# ESP32.net
KiCad netlist of a schematic drawn in Altium Designer
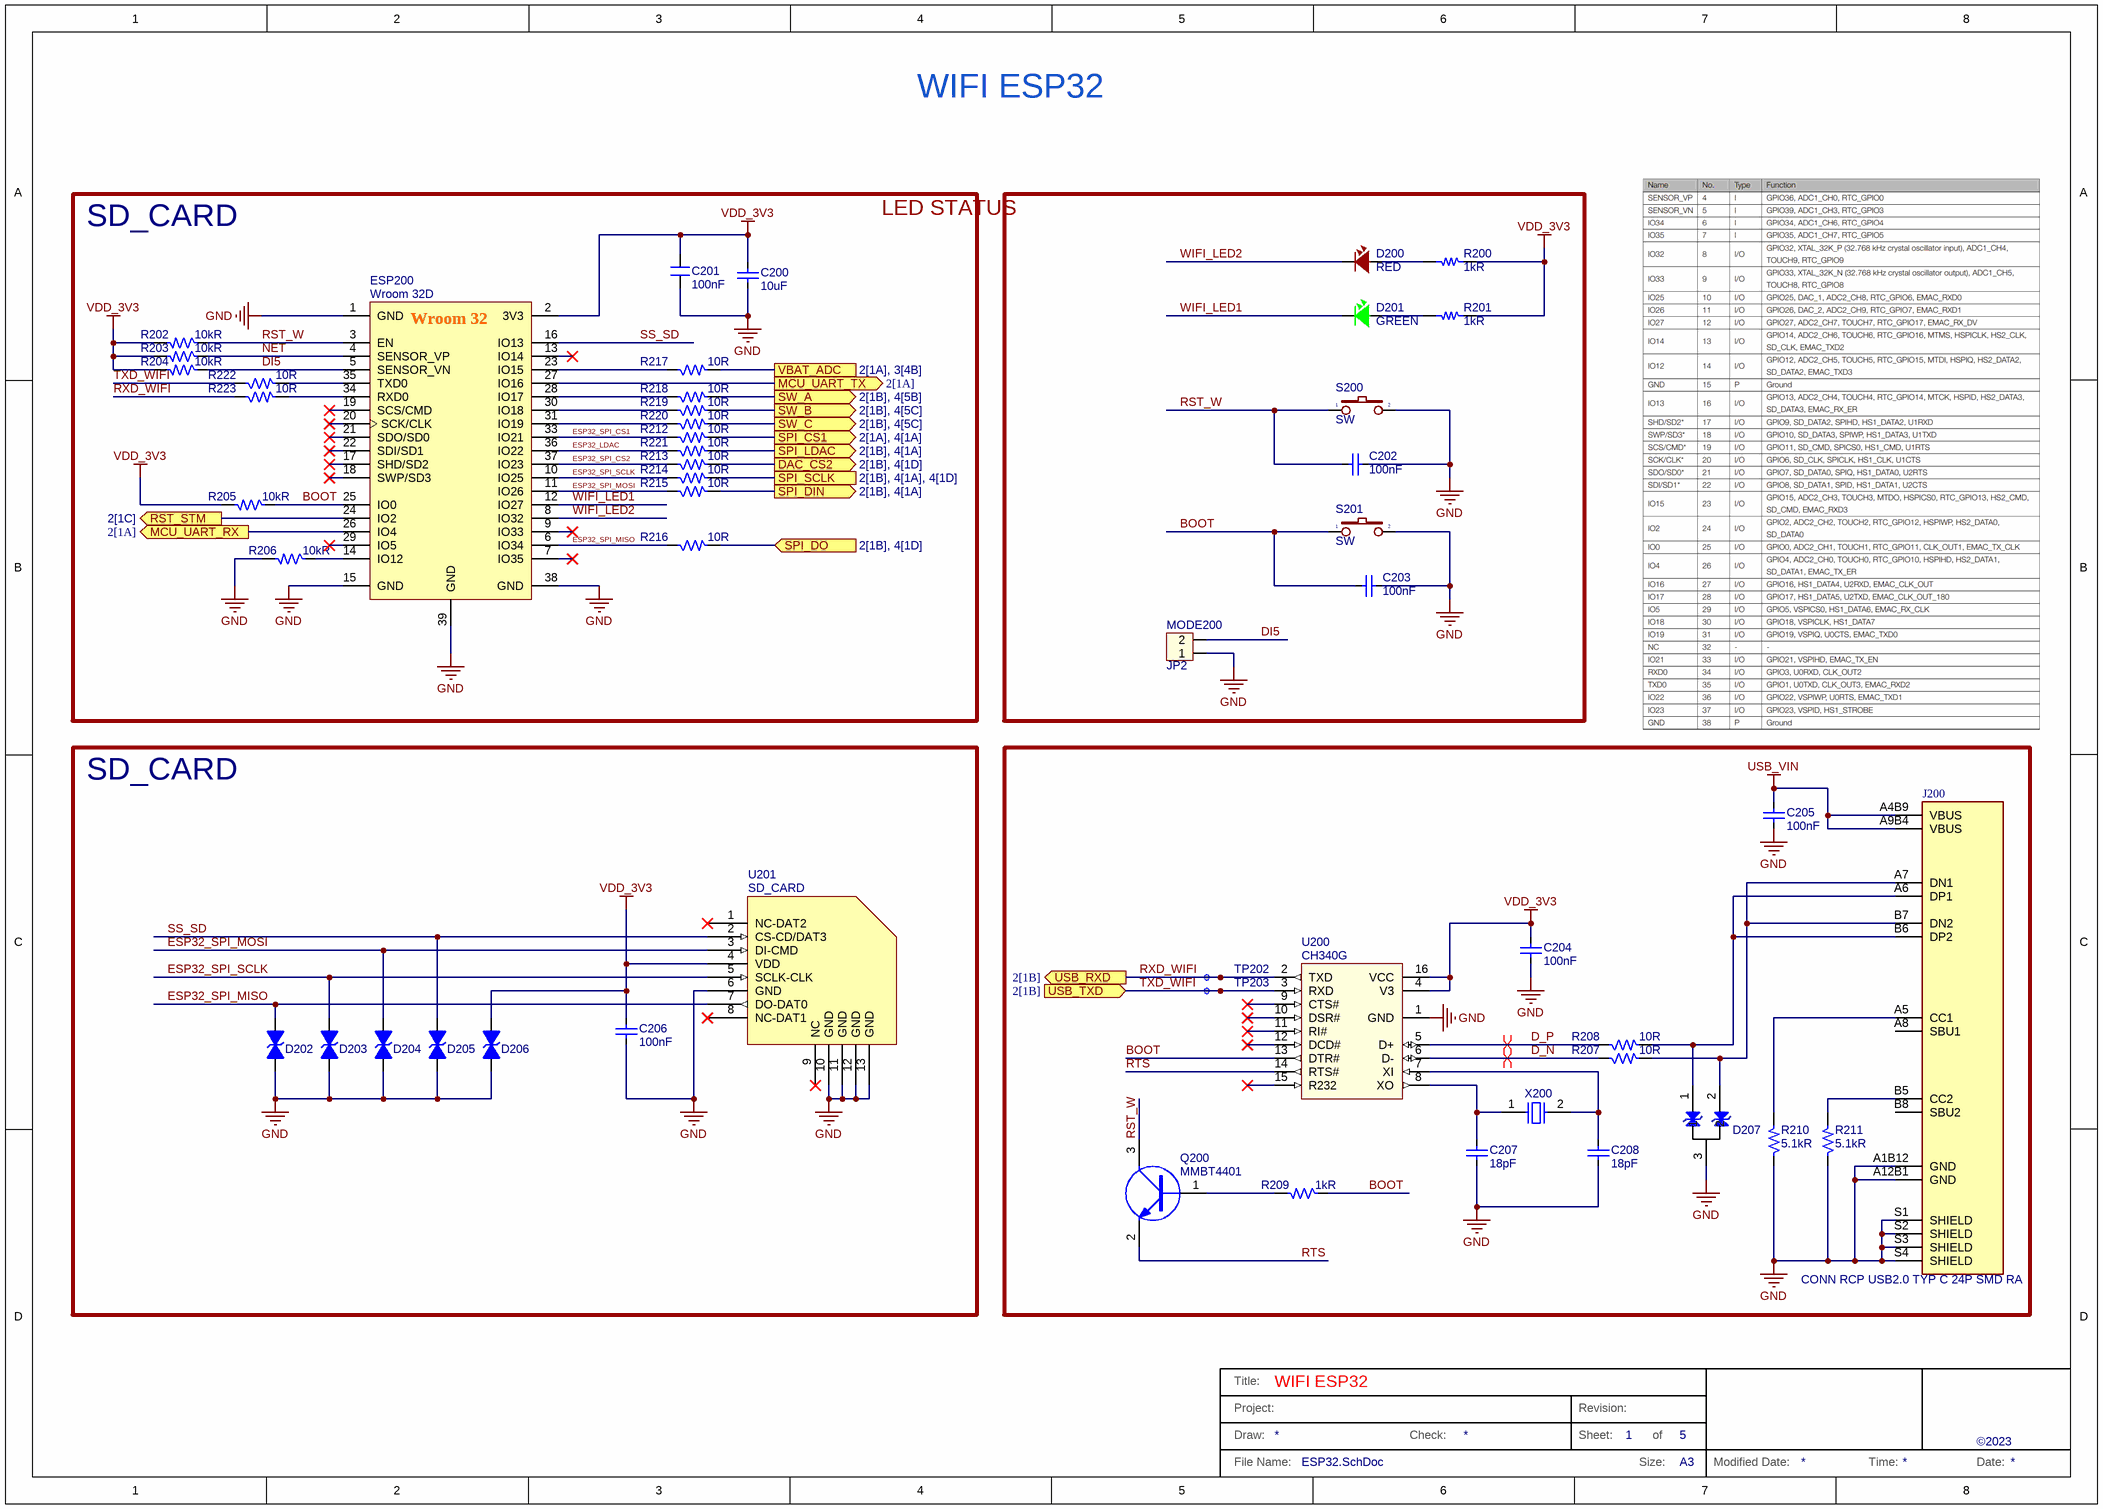
[diagram p0: ESP32.SchDoc]

(export (version "E")
  (design (tool "Eeschema 10.0.6"))
  (components
    (comp (ref "C200")
      (value "10uF")
      (footprint "C0805")
      (description "CAP CER 10UF 16V X5R 0603")
      (libsource (lib "My Library") (part "CapSMD"))
    )
    (comp (ref "C201")
      (value "100nF")
      (footprint "CAP0603-M")
      (description "CAP CER 100nF 16V X5R 0603")
      (fields (field (name "MANUFACTURER") "MURATA"))
      (libsource (lib "Selex_Component_Lib") (part "Cap_Cer_0603_10uF"))
    )
    (comp (ref "C202")
      (value "100nF")
      (footprint "CAP0603-M")
      (description "CAP CER 100nF 16V X5R 0603")
      (libsource (lib "My Library") (part "CapSMD"))
    )
    (comp (ref "C203")
      (value "100nF")
      (footprint "CAP0603-M")
      (description "CAP CER 100nF 16V X5R 0603")
      (libsource (lib "My Library") (part "CapSMD"))
    )
    (comp (ref "C204")
      (value "100nF")
      (footprint "CAP0603-M")
      (description "CAP CER 100nF 16V X5R 0603")
      (libsource (lib "My Library") (part "CapSMD"))
    )
    (comp (ref "C205")
      (value "100nF")
      (footprint "CAP0603-M")
      (description "CAP CER 100nF 16V X5R 0603")
      (libsource (lib "My Library") (part "CapSMD"))
    )
    (comp (ref "C206")
      (value "100nF")
      (footprint "CAP0603-M")
      (description "CAP CER 100nF 16V X5R 0603")
      (libsource (lib "My Library") (part "CapSMD"))
    )
    (comp (ref "C207")
      (value "18pF")
      (footprint "CAP0603-M")
      (description "CAP CER 18PF 50V C0G/NP0 0603")
      (libsource (lib "My Library") (part "CapSMD"))
    )
    (comp (ref "C208")
      (value "18pF")
      (footprint "CAP0603-M")
      (description "CAP CER 18PF 50V C0G/NP0 0603")
      (libsource (lib "My Library") (part "CapSMD"))
    )
    (comp (ref "D200")
      (value "RED")
      (footprint "LED-0603-Red")
      (description "LED RED")
      (libsource (lib "RTLS_Anchor") (part "LED_3"))
    )
    (comp (ref "D201")
      (value "GREEN")
      (footprint "LED-0603-Green")
      (description "LED GREEN")
      (libsource (lib "RTLS_Anchor") (part "LED_1"))
    )
    (comp (ref "D202")
      (value "ESDAXLC6-1BU2")
      (footprint "2-UDFN")
      (description "TVS DIODE 3VWM 17VC ST0201")
      (fields (field (name "MANUFACTURER") "STMicroelectronics"))
      (libsource (lib "RTLS_Anchor") (part "ESDAXLC6-1BU2"))
    )
    (comp (ref "D203")
      (value "ESDAXLC6-1BU2")
      (footprint "2-UDFN")
      (description "TVS DIODE 3VWM 17VC ST0201")
      (fields (field (name "MANUFACTURER") "STMicroelectronics"))
      (libsource (lib "RTLS_Anchor") (part "ESDAXLC6-1BU2"))
    )
    (comp (ref "D204")
      (value "ESDAXLC6-1BU2")
      (footprint "2-UDFN")
      (description "TVS DIODE 3VWM 17VC ST0201")
      (fields (field (name "MANUFACTURER") "STMicroelectronics"))
      (libsource (lib "RTLS_Anchor") (part "ESDAXLC6-1BU2"))
    )
    (comp (ref "D205")
      (value "ESDAXLC6-1BU2")
      (footprint "2-UDFN")
      (description "TVS DIODE 3VWM 17VC ST0201")
      (fields (field (name "MANUFACTURER") "STMicroelectronics"))
      (libsource (lib "RTLS_Anchor") (part "ESDAXLC6-1BU2"))
    )
    (comp (ref "D206")
      (value "ESDAXLC6-1BU2")
      (footprint "2-UDFN")
      (description "TVS DIODE 3VWM 17VC ST0201")
      (fields (field (name "MANUFACTURER") "STMicroelectronics"))
      (libsource (lib "RTLS_Anchor") (part "ESDAXLC6-1BU2"))
    )
    (comp (ref "D207")
      (value "DESD2CAN2SOQ-7")
      (footprint "SOT23-3")
      (description "TVS DIODE 24VWM 41VC SOT23")
      (fields (field (name "MANUFACTURER") "onsemi"))
      (libsource (lib "S1500_Diode") (part "NUP2105"))
    )
    (comp (ref "ESP200")
      (value "Wroom 32D")
      (footprint "ESP32_UE")
      (libsource (lib "PCB_LT") (part "ESP-WROOM-32"))
    )
    (comp (ref "J200")
      (value "CONN RCP USB2.0 TYP C 24P SMD RA")
      (footprint "USB_USB4110-GF-A")
      (description "Conn USB Type C RCP 16 POS 0.3mm/0.5mm Solder ST SMD 16 Terminal 1 Port T/R")
      (libsource (lib "EV_Mainboard") (part "USB_TypeC_USB4110-GF-A"))
    )
    (comp (ref "MODE200")
      (value "JP2")
      (footprint "XH2.54")
      (description "Connector 2")
      (libsource (lib "Anh_Trung") (part "Con2"))
    )
    (comp (ref "Q200")
      (value "MMBT4401")
      (footprint "SOT23-3")
      (description "NPN 600mW, ECB")
      (libsource (lib "Anh_Trung") (part "C1815"))
    )
    (comp (ref "R200")
      (value "1kR")
      (footprint "R_0603")
      (description "RES SMD 1K OHM 1% 1/8W 0603")
      (fields (field (name "MANUFACTURER") "Generic Components"))
      (libsource (lib "My Library") (part "Resistor - SMD"))
    )
    (comp (ref "R201")
      (value "1kR")
      (footprint "R_0603")
      (description "RES SMD 1K OHM 1% 1/8W 0603")
      (fields (field (name "MANUFACTURER") "Generic Components"))
      (libsource (lib "My Library") (part "Resistor - SMD"))
    )
    (comp (ref "R202")
      (value "10kR")
      (footprint "R_0603")
      (description "RES SMD 10K OHM 1% 1/8W 0603")
      (fields (field (name "MANUFACTURER") "Yageo"))
      (libsource (lib "Anh_Trung") (part "R"))
    )
    (comp (ref "R203")
      (value "10kR")
      (footprint "R_0603")
      (description "RES SMD 10K OHM 1% 1/8W 0603")
      (fields (field (name "MANUFACTURER") "Yageo"))
      (libsource (lib "Anh_Trung") (part "R"))
    )
    (comp (ref "R204")
      (value "10kR")
      (footprint "R_0603")
      (description "RES SMD 10K OHM 1% 1/8W 0603")
      (fields (field (name "MANUFACTURER") "Yageo"))
      (libsource (lib "Anh_Trung") (part "R"))
    )
    (comp (ref "R205")
      (value "10kR")
      (footprint "R_0603")
      (description "RES SMD 10K OHM 1% 1/8W 0603")
      (fields (field (name "MANUFACTURER") "Yageo"))
      (libsource (lib "Anh_Trung") (part "R"))
    )
    (comp (ref "R206")
      (value "10kR")
      (footprint "R_0603")
      (description "RES SMD 10K OHM 1% 1/8W 0603")
      (fields (field (name "MANUFACTURER") "Yageo"))
      (libsource (lib "Anh_Trung") (part "R"))
    )
    (comp (ref "R207")
      (value "10R")
      (footprint "R_0603")
      (description "RES SMD 10R OHM 1% 1/8W 0603")
      (fields (field (name "MANUFACTURER") "Yageo"))
      (libsource (lib "Anh_Trung") (part "R"))
    )
    (comp (ref "R208")
      (value "10R")
      (footprint "R_0603")
      (description "RES SMD 10R OHM 1% 1/8W 0603")
      (fields (field (name "MANUFACTURER") "Yageo"))
      (libsource (lib "Anh_Trung") (part "R"))
    )
    (comp (ref "R209")
      (value "1kR")
      (footprint "R_0603")
      (description "RES SMD 1K OHM 1% 1/8W 0603")
      (fields (field (name "MANUFACTURER") "Yageo"))
      (libsource (lib "Anh_Trung") (part "R"))
    )
    (comp (ref "R210")
      (value "5.1kR")
      (footprint "R_0603")
      (description "Resistor 1/4W")
      (fields (field (name "MANUFACTURER") "Yageo"))
      (libsource (lib "Anh_Trung") (part "R"))
    )
    (comp (ref "R211")
      (value "5.1kR")
      (footprint "R_0603")
      (description "Resistor 1/4W")
      (fields (field (name "MANUFACTURER") "Yageo"))
      (libsource (lib "Anh_Trung") (part "R"))
    )
    (comp (ref "R212")
      (value "10R")
      (footprint "R_0603")
      (description "RES SMD 10R OHM 1% 1/8W 0603")
      (fields (field (name "MANUFACTURER") "Yageo"))
      (libsource (lib "Anh_Trung") (part "R"))
    )
    (comp (ref "R213")
      (value "10R")
      (footprint "R_0603")
      (description "RES SMD 10R OHM 1% 1/8W 0603")
      (fields (field (name "MANUFACTURER") "Yageo"))
      (libsource (lib "Anh_Trung") (part "R"))
    )
    (comp (ref "R214")
      (value "10R")
      (footprint "R_0603")
      (description "RES SMD 10R OHM 1% 1/8W 0603")
      (fields (field (name "MANUFACTURER") "Yageo"))
      (libsource (lib "Anh_Trung") (part "R"))
    )
    (comp (ref "R215")
      (value "10R")
      (footprint "R_0603")
      (description "RES SMD 10R OHM 1% 1/8W 0603")
      (fields (field (name "MANUFACTURER") "Yageo"))
      (libsource (lib "Anh_Trung") (part "R"))
    )
    (comp (ref "R216")
      (value "10R")
      (footprint "R_0603")
      (description "RES SMD 10R OHM 1% 1/8W 0603")
      (fields (field (name "MANUFACTURER") "Yageo"))
      (libsource (lib "Anh_Trung") (part "R"))
    )
    (comp (ref "R217")
      (value "10R")
      (footprint "R_0603")
      (description "RES SMD 10R OHM 1% 1/8W 0603")
      (fields (field (name "MANUFACTURER") "Yageo"))
      (libsource (lib "Anh_Trung") (part "R"))
    )
    (comp (ref "R218")
      (value "10R")
      (footprint "R_0603")
      (description "RES SMD 10R OHM 1% 1/8W 0603")
      (fields (field (name "MANUFACTURER") "Yageo"))
      (libsource (lib "Anh_Trung") (part "R"))
    )
    (comp (ref "R219")
      (value "10R")
      (footprint "R_0603")
      (description "RES SMD 10R OHM 1% 1/8W 0603")
      (fields (field (name "MANUFACTURER") "Yageo"))
      (libsource (lib "Anh_Trung") (part "R"))
    )
    (comp (ref "R220")
      (value "10R")
      (footprint "R_0603")
      (description "RES SMD 10R OHM 1% 1/8W 0603")
      (fields (field (name "MANUFACTURER") "Yageo"))
      (libsource (lib "Anh_Trung") (part "R"))
    )
    (comp (ref "R221")
      (value "10R")
      (footprint "R_0603")
      (description "RES SMD 10R OHM 1% 1/8W 0603")
      (fields (field (name "MANUFACTURER") "Yageo"))
      (libsource (lib "Anh_Trung") (part "R"))
    )
    (comp (ref "R222")
      (value "10R")
      (footprint "R_0603")
      (description "RES SMD 10R OHM 1% 1/8W 0603")
      (fields (field (name "MANUFACTURER") "Yageo"))
      (libsource (lib "Anh_Trung") (part "R"))
    )
    (comp (ref "R223")
      (value "10R")
      (footprint "R_0603")
      (description "RES SMD 10R OHM 1% 1/8W 0603")
      (fields (field (name "MANUFACTURER") "Yageo"))
      (libsource (lib "Anh_Trung") (part "R"))
    )
    (comp (ref "S200")
      (value "SW")
      (footprint "BUTTON_2P_SMD")
      (description "Switch button 2 pin")
      (libsource (lib "Anh_Trung") (part "SW2"))
    )
    (comp (ref "S201")
      (value "SW")
      (footprint "BUTTON_2P_SMD")
      (description "Switch button 2 pin")
      (libsource (lib "Anh_Trung") (part "SW2"))
    )
    (comp (ref "TP202")
      (value "RXD")
      (footprint "TPH")
      (description "Test_Point_1mm")
      (libsource (lib "Selex_Component_Lib") (part "Test_Point_1mm"))
    )
    (comp (ref "TP203")
      (value "TXD")
      (footprint "TPH")
      (description "Test_Point_1mm")
      (libsource (lib "Selex_Component_Lib") (part "Test_Point_1mm"))
    )
    (comp (ref "U200")
      (value "CH340G")
      (footprint "SOIC-16")
      (description "USB to UART Interface")
      (fields (field (name "MANUFACTURER") "WCH"))
      (libsource (lib "Anh_Trung") (part "CH340G"))
    )
    (comp (ref "U201")
      (value "SD_CARD")
      (footprint "MICROSD2")
      (description "SD/MMC holder")
      (libsource (lib "Anh_Trung") (part "MicroSD"))
    )
    (comp (ref "X200")
      (value "WTL5G60391VH")
      (footprint "XTAL_SMD_3P5")
      (description "XTal 8Mhz")
      (fields (field (name "MANUFACTURER") "WTL"))
      (libsource (lib "S1600_Crystal_Oscillator") (part "Xtal_2P_SMD_5P0X3P5_8Mhz"))
    )
  )
  (nets
    (net (code "1") (name "/BOOT") (class "Default")
      (node (ref "C203") (pin "2") (pinfunction "2_2") (pintype "passive"))
      (node (ref "ESP200") (pin "25") (pinfunction "IO0_25") (pintype "passive"))
      (node (ref "R205") (pin "1") (pinfunction "1_1") (pintype "passive"))
      (node (ref "R209") (pin "1") (pinfunction "1_1") (pintype "passive"))
      (node (ref "S201") (pin "1") (pinfunction "1_1") (pintype "passive"))
      (node (ref "U200") (pin "13") (pinfunction "DTR#_13") (pintype "output"))
    )
    (net (code "2") (name "/DAC_CS2") (class "Default")
      (node (ref "R213") (pin "2") (pinfunction "2_2") (pintype "passive"))
    )
    (net (code "3") (name "/DI5") (class "Default")
      (node (ref "ESP200") (pin "5") (pinfunction "SENSOR_VN_5") (pintype "passive"))
      (node (ref "MODE200") (pin "2") (pinfunction "2_2") (pintype "passive"))
      (node (ref "R204") (pin "1") (pinfunction "1_1") (pintype "passive"))
    )
    (net (code "4") (name "/D_N") (class "Default")
      (node (ref "R207") (pin "1") (pinfunction "1_1") (pintype "passive"))
      (node (ref "U200") (pin "6") (pinfunction "D-_6") (pintype "bidirectional"))
    )
    (net (code "5") (name "/D_P") (class "Default")
      (node (ref "R208") (pin "1") (pinfunction "1_1") (pintype "passive"))
      (node (ref "U200") (pin "5") (pinfunction "D+_5") (pintype "bidirectional"))
    )
    (net (code "6") (name "/ESP32_LDAC") (class "Default")
      (node (ref "ESP200") (pin "36") (pinfunction "IO22_36") (pintype "passive"))
      (node (ref "R221") (pin "1") (pinfunction "1_1") (pintype "passive"))
    )
    (net (code "7") (name "/ESP32_SPI_CS1") (class "Default")
      (node (ref "ESP200") (pin "33") (pinfunction "IO21_33") (pintype "passive"))
      (node (ref "R212") (pin "1") (pinfunction "1_1") (pintype "passive"))
    )
    (net (code "8") (name "/ESP32_SPI_CS2") (class "Default")
      (node (ref "ESP200") (pin "37") (pinfunction "IO23_37") (pintype "passive"))
      (node (ref "R213") (pin "1") (pinfunction "1_1") (pintype "passive"))
    )
    (net (code "9") (name "/ESP32_SPI_MISO") (class "Default")
      (node (ref "D202") (pin "1") (pinfunction "A_1") (pintype "passive"))
      (node (ref "ESP200") (pin "6") (pinfunction "IO34_6") (pintype "passive"))
      (node (ref "R216") (pin "1") (pinfunction "1_1") (pintype "passive"))
      (node (ref "U201") (pin "7") (pinfunction "DO-DAT0_7") (pintype "output"))
    )
    (net (code "10") (name "/ESP32_SPI_MOSI") (class "Default")
      (node (ref "D204") (pin "1") (pinfunction "A_1") (pintype "passive"))
      (node (ref "ESP200") (pin "11") (pinfunction "IO26_11") (pintype "passive"))
      (node (ref "R215") (pin "1") (pinfunction "1_1") (pintype "passive"))
      (node (ref "U201") (pin "3") (pinfunction "DI-CMD_3") (pintype "input"))
    )
    (net (code "11") (name "/ESP32_SPI_SCLK") (class "Default")
      (node (ref "D203") (pin "1") (pinfunction "A_1") (pintype "passive"))
      (node (ref "ESP200") (pin "10") (pinfunction "IO25_10") (pintype "passive"))
      (node (ref "R214") (pin "1") (pinfunction "1_1") (pintype "passive"))
      (node (ref "U201") (pin "5") (pinfunction "SCLK-CLK_5") (pintype "input"))
    )
    (net (code "12") (name "/MCU_UART_RX") (class "Default")
      (node (ref "ESP200") (pin "26") (pinfunction "IO4_26") (pintype "passive"))
    )
    (net (code "13") (name "/MCU_UART_TX") (class "Default")
      (node (ref "ESP200") (pin "27") (pinfunction "IO16_27") (pintype "passive"))
    )
    (net (code "14") (name "/NET") (class "Default")
      (node (ref "ESP200") (pin "4") (pinfunction "SENSOR_VP_4") (pintype "passive"))
      (node (ref "R203") (pin "1") (pinfunction "1_1") (pintype "passive"))
    )
    (net (code "15") (name "/RST_STM") (class "Default")
      (node (ref "ESP200") (pin "24") (pinfunction "IO2_24") (pintype "passive"))
    )
    (net (code "16") (name "/RST_W") (class "Default")
      (node (ref "C202") (pin "2") (pinfunction "2_2") (pintype "passive"))
      (node (ref "ESP200") (pin "3") (pinfunction "EN_3") (pintype "passive"))
      (node (ref "Q200") (pin "3") (pinfunction "C_3") (pintype "passive"))
      (node (ref "R202") (pin "1") (pinfunction "1_1") (pintype "passive"))
      (node (ref "S200") (pin "1") (pinfunction "1_1") (pintype "passive"))
    )
    (net (code "17") (name "/RTS") (class "Default")
      (node (ref "Q200") (pin "2") (pinfunction "E_2") (pintype "passive"))
      (node (ref "U200") (pin "14") (pinfunction "RTS#_14") (pintype "output"))
    )
    (net (code "18") (name "/RXD_WIFI") (class "Default")
      (node (ref "R223") (pin "1") (pinfunction "1_1") (pintype "passive"))
      (node (ref "TP202") (pin "1") (pinfunction "TP_1") (pintype "passive"))
      (node (ref "U200") (pin "2") (pinfunction "TXD_2") (pintype "output"))
    )
    (net (code "19") (name "/SPI_CS1") (class "Default")
      (node (ref "R212") (pin "2") (pinfunction "2_2") (pintype "passive"))
    )
    (net (code "20") (name "/SPI_DIN") (class "Default")
      (node (ref "R215") (pin "2") (pinfunction "2_2") (pintype "passive"))
    )
    (net (code "21") (name "/SPI_DO") (class "Default")
      (node (ref "R216") (pin "2") (pinfunction "2_2") (pintype "passive"))
    )
    (net (code "22") (name "/SPI_LDAC") (class "Default")
      (node (ref "R221") (pin "2") (pinfunction "2_2") (pintype "passive"))
    )
    (net (code "23") (name "/SPI_SCLK") (class "Default")
      (node (ref "R214") (pin "2") (pinfunction "2_2") (pintype "passive"))
    )
    (net (code "24") (name "/SS_SD") (class "Default")
      (node (ref "D205") (pin "1") (pinfunction "A_1") (pintype "passive"))
      (node (ref "ESP200") (pin "16") (pinfunction "IO13_16") (pintype "passive"))
      (node (ref "U201") (pin "2") (pinfunction "CS-CD/DAT3_2") (pintype "input"))
    )
    (net (code "25") (name "/SW_A") (class "Default")
      (node (ref "R218") (pin "2") (pinfunction "2_2") (pintype "passive"))
    )
    (net (code "26") (name "/SW_B") (class "Default")
      (node (ref "R219") (pin "2") (pinfunction "2_2") (pintype "passive"))
    )
    (net (code "27") (name "/SW_C") (class "Default")
      (node (ref "R220") (pin "2") (pinfunction "2_2") (pintype "passive"))
    )
    (net (code "28") (name "/TXD_WIFI") (class "Default")
      (node (ref "R222") (pin "1") (pinfunction "1_1") (pintype "passive"))
      (node (ref "TP203") (pin "1") (pinfunction "TP_1") (pintype "passive"))
      (node (ref "U200") (pin "3") (pinfunction "RXD_3") (pintype "input"))
    )
    (net (code "29") (name "/VBAT_ADC") (class "Default")
      (node (ref "R217") (pin "2") (pinfunction "2_2") (pintype "passive"))
    )
    (net (code "30") (name "/WIFI_LED1") (class "Default")
      (node (ref "D201") (pin "2") (pinfunction "2_2") (pintype "passive"))
      (node (ref "ESP200") (pin "12") (pinfunction "IO27_12") (pintype "passive"))
    )
    (net (code "31") (name "/WIFI_LED2") (class "Default")
      (node (ref "D200") (pin "2") (pinfunction "2_2") (pintype "passive"))
      (node (ref "ESP200") (pin "8") (pinfunction "IO32_8") (pintype "passive"))
    )
    (net (code "32") (name "GND") (class "Default")
      (node (ref "C200") (pin "1") (pinfunction "1_1") (pintype "passive"))
      (node (ref "C201") (pin "1") (pinfunction "1_1") (pintype "passive"))
      (node (ref "C202") (pin "1") (pinfunction "1_1") (pintype "passive"))
      (node (ref "C203") (pin "1") (pinfunction "1_1") (pintype "passive"))
      (node (ref "C204") (pin "1") (pinfunction "1_1") (pintype "passive"))
      (node (ref "C205") (pin "1") (pinfunction "1_1") (pintype "passive"))
      (node (ref "C206") (pin "1") (pinfunction "1_1") (pintype "passive"))
      (node (ref "C207") (pin "2") (pinfunction "2_2") (pintype "passive"))
      (node (ref "C208") (pin "2") (pinfunction "2_2") (pintype "passive"))
      (node (ref "D202") (pin "2") (pinfunction "K_2") (pintype "passive"))
      (node (ref "D203") (pin "2") (pinfunction "K_2") (pintype "passive"))
      (node (ref "D204") (pin "2") (pinfunction "K_2") (pintype "passive"))
      (node (ref "D205") (pin "2") (pinfunction "K_2") (pintype "passive"))
      (node (ref "D206") (pin "2") (pinfunction "K_2") (pintype "passive"))
      (node (ref "D207") (pin "3") (pinfunction "3_3") (pintype "passive"))
      (node (ref "ESP200") (pin "1") (pinfunction "GND_1") (pintype "power_in"))
      (node (ref "ESP200") (pin "15") (pinfunction "GND_15") (pintype "power_in"))
      (node (ref "ESP200") (pin "38") (pinfunction "GND_38") (pintype "power_in"))
      (node (ref "ESP200") (pin "39") (pinfunction "GND_39") (pintype "power_in"))
      (node (ref "J200") (pin "A12B1") (pinfunction "GND_A12B1") (pintype "passive"))
      (node (ref "J200") (pin "A1B12") (pinfunction "GND_A1B12") (pintype "passive"))
      (node (ref "J200") (pin "S1") (pinfunction "SHIELD_S1") (pintype "passive"))
      (node (ref "J200") (pin "S2") (pinfunction "SHIELD_S2") (pintype "passive"))
      (node (ref "J200") (pin "S3") (pinfunction "SHIELD_S3") (pintype "passive"))
      (node (ref "J200") (pin "S4") (pinfunction "SHIELD_S4") (pintype "passive"))
      (node (ref "MODE200") (pin "1") (pinfunction "1_1") (pintype "passive"))
      (node (ref "R206") (pin "2") (pinfunction "2_2") (pintype "passive"))
      (node (ref "R210") (pin "1") (pinfunction "1_1") (pintype "passive"))
      (node (ref "R211") (pin "1") (pinfunction "1_1") (pintype "passive"))
      (node (ref "S200") (pin "2") (pinfunction "2_2") (pintype "passive"))
      (node (ref "S201") (pin "2") (pinfunction "2_2") (pintype "passive"))
      (node (ref "U200") (pin "1") (pinfunction "GND_1") (pintype "passive"))
      (node (ref "U201") (pin "10") (pinfunction "GND_10") (pintype "passive"))
      (node (ref "U201") (pin "11") (pinfunction "GND_11") (pintype "passive"))
      (node (ref "U201") (pin "12") (pinfunction "GND_12") (pintype "passive"))
      (node (ref "U201") (pin "13") (pinfunction "GND_13") (pintype "passive"))
      (node (ref "U201") (pin "6") (pinfunction "GND_6") (pintype "passive"))
    )
    (net (code "33") (name "Net-(D200-Pad1)") (class "Default")
      (node (ref "D200") (pin "1") (pinfunction "1_1") (pintype "passive"))
      (node (ref "R200") (pin "1") (pinfunction "1_1") (pintype "passive"))
    )
    (net (code "34") (name "Net-(D201-Pad1)") (class "Default")
      (node (ref "D201") (pin "1") (pinfunction "1_1") (pintype "passive"))
      (node (ref "R201") (pin "1") (pinfunction "1_1") (pintype "passive"))
    )
    (net (code "35") (name "Net-(ESP200-IO12)") (class "Default")
      (node (ref "ESP200") (pin "14") (pinfunction "IO12_14") (pintype "passive"))
      (node (ref "R206") (pin "1") (pinfunction "1_1") (pintype "passive"))
    )
    (net (code "36") (name "Net-(ESP200-IO15)") (class "Default")
      (node (ref "ESP200") (pin "23") (pinfunction "IO15_23") (pintype "passive"))
      (node (ref "R217") (pin "1") (pinfunction "1_1") (pintype "passive"))
    )
    (net (code "37") (name "Net-(ESP200-IO17)") (class "Default")
      (node (ref "ESP200") (pin "28") (pinfunction "IO17_28") (pintype "passive"))
      (node (ref "R218") (pin "1") (pinfunction "1_1") (pintype "passive"))
    )
    (net (code "38") (name "Net-(ESP200-IO18)") (class "Default")
      (node (ref "ESP200") (pin "30") (pinfunction "IO18_30") (pintype "passive"))
      (node (ref "R219") (pin "1") (pinfunction "1_1") (pintype "passive"))
    )
    (net (code "39") (name "Net-(ESP200-IO19)") (class "Default")
      (node (ref "ESP200") (pin "31") (pinfunction "IO19_31") (pintype "passive"))
      (node (ref "R220") (pin "1") (pinfunction "1_1") (pintype "passive"))
    )
    (net (code "40") (name "Net-(ESP200-RXD0)") (class "Default")
      (node (ref "ESP200") (pin "34") (pinfunction "RXD0_34") (pintype "passive"))
      (node (ref "R223") (pin "2") (pinfunction "2_2") (pintype "passive"))
    )
    (net (code "41") (name "Net-(ESP200-TXD0)") (class "Default")
      (node (ref "ESP200") (pin "35") (pinfunction "TXD0_35") (pintype "passive"))
      (node (ref "R222") (pin "2") (pinfunction "2_2") (pintype "passive"))
    )
    (net (code "42") (name "Net-(J200-CC1)") (class "Default")
      (node (ref "J200") (pin "A5") (pinfunction "CC1_A5") (pintype "passive"))
      (node (ref "R210") (pin "2") (pinfunction "2_2") (pintype "passive"))
    )
    (net (code "43") (name "Net-(J200-CC2)") (class "Default")
      (node (ref "J200") (pin "B5") (pinfunction "CC2_B5") (pintype "passive"))
      (node (ref "R211") (pin "2") (pinfunction "2_2") (pintype "passive"))
    )
    (net (code "44") (name "Net-(J200-DN1)") (class "Default")
      (node (ref "D207") (pin "2") (pinfunction "2_2") (pintype "passive"))
      (node (ref "J200") (pin "A7") (pinfunction "DN1_A7") (pintype "passive"))
      (node (ref "J200") (pin "B7") (pinfunction "DN2_B7") (pintype "passive"))
      (node (ref "R207") (pin "2") (pinfunction "2_2") (pintype "passive"))
    )
    (net (code "45") (name "Net-(J200-DP1)") (class "Default")
      (node (ref "D207") (pin "1") (pinfunction "1_1") (pintype "passive"))
      (node (ref "J200") (pin "A6") (pinfunction "DP1_A6") (pintype "passive"))
      (node (ref "J200") (pin "B6") (pinfunction "DP2_B6") (pintype "passive"))
      (node (ref "R208") (pin "2") (pinfunction "2_2") (pintype "passive"))
    )
    (net (code "46") (name "Net-(Q200-B)") (class "Default")
      (node (ref "Q200") (pin "1") (pinfunction "B_1") (pintype "passive"))
      (node (ref "R209") (pin "2") (pinfunction "2_2") (pintype "passive"))
    )
    (net (code "47") (name "Net-(U200-XI)") (class "Default")
      (node (ref "C208") (pin "1") (pinfunction "1_1") (pintype "passive"))
      (node (ref "U200") (pin "7") (pinfunction "XI_7") (pintype "input"))
      (node (ref "X200") (pin "2") (pinfunction "2_2") (pintype "passive"))
    )
    (net (code "48") (name "Net-(U200-XO)") (class "Default")
      (node (ref "C207") (pin "1") (pinfunction "1_1") (pintype "passive"))
      (node (ref "U200") (pin "8") (pinfunction "XO_8") (pintype "output"))
      (node (ref "X200") (pin "1") (pinfunction "1_1") (pintype "passive"))
    )
    (net (code "49") (name "USB_VIN") (class "Default")
      (node (ref "C205") (pin "2") (pinfunction "2_2") (pintype "passive"))
      (node (ref "J200") (pin "A4B9") (pinfunction "VBUS_A4B9") (pintype "passive"))
      (node (ref "J200") (pin "A9B4") (pinfunction "VBUS_A9B4") (pintype "passive"))
    )
    (net (code "50") (name "VDD_3V3") (class "Default")
      (node (ref "C200") (pin "2") (pinfunction "2_2") (pintype "passive"))
      (node (ref "C201") (pin "2") (pinfunction "2_2") (pintype "passive"))
      (node (ref "C204") (pin "2") (pinfunction "2_2") (pintype "passive"))
      (node (ref "C206") (pin "2") (pinfunction "2_2") (pintype "passive"))
      (node (ref "D206") (pin "1") (pinfunction "A_1") (pintype "passive"))
      (node (ref "ESP200") (pin "2") (pinfunction "3V3_2") (pintype "power_in"))
      (node (ref "R200") (pin "2") (pinfunction "2_2") (pintype "passive"))
      (node (ref "R201") (pin "2") (pinfunction "2_2") (pintype "passive"))
      (node (ref "R202") (pin "2") (pinfunction "2_2") (pintype "passive"))
      (node (ref "R203") (pin "2") (pinfunction "2_2") (pintype "passive"))
      (node (ref "R204") (pin "2") (pinfunction "2_2") (pintype "passive"))
      (node (ref "R205") (pin "2") (pinfunction "2_2") (pintype "passive"))
      (node (ref "U200") (pin "16") (pinfunction "VCC_16") (pintype "power_in"))
      (node (ref "U200") (pin "4") (pinfunction "V3_4") (pintype "passive"))
      (node (ref "U201") (pin "4") (pinfunction "VDD_4") (pintype "passive"))
    )
    (net (code "51") (name "unconnected-(ESP200-IO5-Pad29)") (class "Default")
      (node (ref "ESP200") (pin "29") (pinfunction "IO5_29") (pintype "passive+no_connect"))
    )
    (net (code "52") (name "unconnected-(ESP200-IO14-Pad13)") (class "Default")
      (node (ref "ESP200") (pin "13") (pinfunction "IO14_13") (pintype "passive+no_connect"))
    )
    (net (code "53") (name "unconnected-(ESP200-IO33-Pad9)") (class "Default")
      (node (ref "ESP200") (pin "9") (pinfunction "IO33_9") (pintype "passive+no_connect"))
    )
    (net (code "54") (name "unconnected-(ESP200-IO35-Pad7)") (class "Default")
      (node (ref "ESP200") (pin "7") (pinfunction "IO35_7") (pintype "passive+no_connect"))
    )
    (net (code "55") (name "unconnected-(ESP200-SCK{slash}CLK-Pad20)") (class "Default")
      (node (ref "ESP200") (pin "20") (pinfunction "SCK/CLK_20") (pintype "passive+no_connect"))
    )
    (net (code "56") (name "unconnected-(ESP200-SCS{slash}CMD-Pad19)") (class "Default")
      (node (ref "ESP200") (pin "19") (pinfunction "SCS/CMD_19") (pintype "passive+no_connect"))
    )
    (net (code "57") (name "unconnected-(ESP200-SDI{slash}SD1-Pad22)") (class "Default")
      (node (ref "ESP200") (pin "22") (pinfunction "SDI/SD1_22") (pintype "passive+no_connect"))
    )
    (net (code "58") (name "unconnected-(ESP200-SDO{slash}SD0-Pad21)") (class "Default")
      (node (ref "ESP200") (pin "21") (pinfunction "SDO/SD0_21") (pintype "passive+no_connect"))
    )
    (net (code "59") (name "unconnected-(ESP200-SHD{slash}SD2-Pad17)") (class "Default")
      (node (ref "ESP200") (pin "17") (pinfunction "SHD/SD2_17") (pintype "passive+no_connect"))
    )
    (net (code "60") (name "unconnected-(ESP200-SWP{slash}SD3-Pad18)") (class "Default")
      (node (ref "ESP200") (pin "18") (pinfunction "SWP/SD3_18") (pintype "passive+no_connect"))
    )
    (net (code "61") (name "unconnected-(J200-SBU1-PadA8)") (class "Default")
      (node (ref "J200") (pin "A8") (pinfunction "SBU1_A8") (pintype "passive"))
    )
    (net (code "62") (name "unconnected-(J200-SBU2-PadB8)") (class "Default")
      (node (ref "J200") (pin "B8") (pinfunction "SBU2_B8") (pintype "passive"))
    )
    (net (code "63") (name "unconnected-(U200-CTS#-Pad9)") (class "Default")
      (node (ref "U200") (pin "9") (pinfunction "CTS#_9") (pintype "input+no_connect"))
    )
    (net (code "64") (name "unconnected-(U200-DCD#-Pad12)") (class "Default")
      (node (ref "U200") (pin "12") (pinfunction "DCD#_12") (pintype "input+no_connect"))
    )
    (net (code "65") (name "unconnected-(U200-DSR#-Pad10)") (class "Default")
      (node (ref "U200") (pin "10") (pinfunction "DSR#_10") (pintype "input+no_connect"))
    )
    (net (code "66") (name "unconnected-(U200-R232-Pad15)") (class "Default")
      (node (ref "U200") (pin "15") (pinfunction "R232_15") (pintype "input+no_connect"))
    )
    (net (code "67") (name "unconnected-(U200-RI#-Pad11)") (class "Default")
      (node (ref "U200") (pin "11") (pinfunction "RI#_11") (pintype "input+no_connect"))
    )
    (net (code "68") (name "unconnected-(U201-NC-DAT1-Pad8)") (class "Default")
      (node (ref "U201") (pin "8") (pinfunction "NC-DAT1_8") (pintype "passive+no_connect"))
    )
    (net (code "69") (name "unconnected-(U201-NC-DAT2-Pad1)") (class "Default")
      (node (ref "U201") (pin "1") (pinfunction "NC-DAT2_1") (pintype "passive+no_connect"))
    )
    (net (code "70") (name "unconnected-(U201-NC-Pad9)") (class "Default")
      (node (ref "U201") (pin "9") (pinfunction "NC_9") (pintype "passive+no_connect"))
    )
  )
)
